# 23D_ESC_DRIVER.net
KiCad netlist of a schematic drawn in Altium Designer
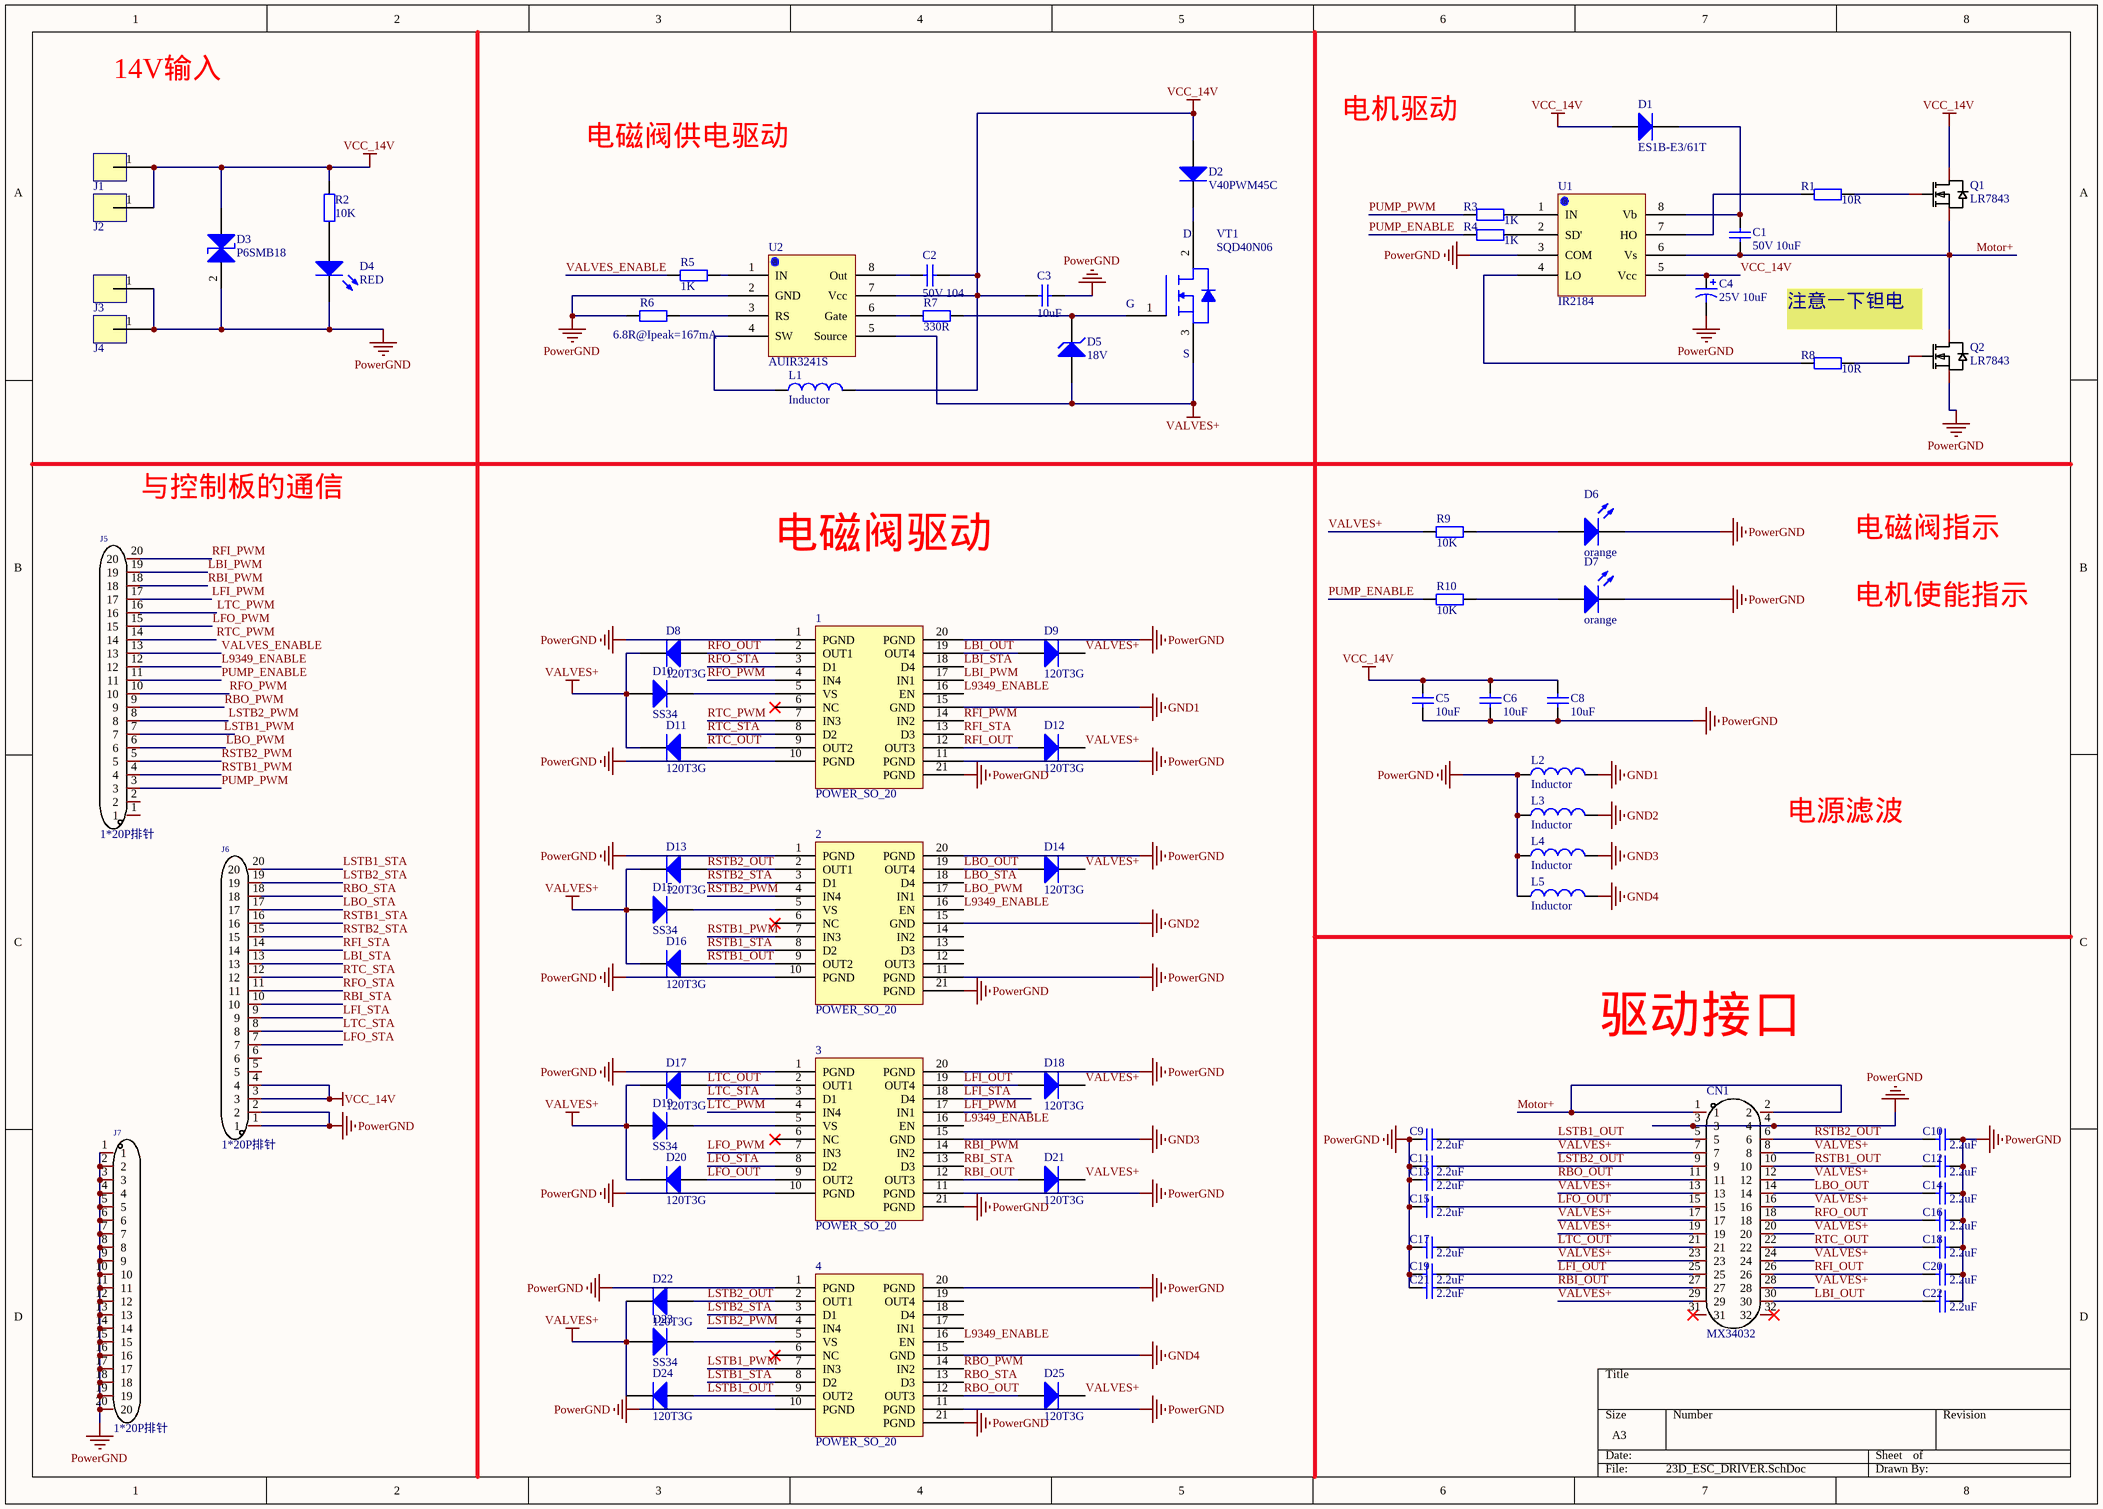
[diagram p0: 23D_ESC_DRIVER.SchDoc]

(export (version "E")
  (design (tool "Eeschema 10.0.6"))
  (components
    (comp (ref "1")
      (value "POWER_SO_20")
      (footprint "POWERSO-20_self_with3D_USEable:POWERSO-20_L15.9-W11.0-P1.27-LS14.2-BL-EP")
      (libsource (lib "PowerSO-20") (part "POWER_SO_20"))
    )
    (comp (ref "2")
      (value "POWER_SO_20")
      (footprint "POWERSO-20_self_with3D_USEable:POWERSO-20_L15.9-W11.0-P1.27-LS14.2-BL-EP")
      (libsource (lib "PowerSO-20") (part "POWER_SO_20"))
    )
    (comp (ref "3")
      (value "POWER_SO_20")
      (footprint "POWERSO-20_self_with3D_USEable:POWERSO-20_L15.9-W11.0-P1.27-LS14.2-BL-EP")
      (libsource (lib "PowerSO-20") (part "POWER_SO_20"))
    )
    (comp (ref "4")
      (value "POWER_SO_20")
      (footprint "POWERSO-20_self_with3D_USEable:POWERSO-20_L15.9-W11.0-P1.27-LS14.2-BL-EP")
      (libsource (lib "PowerSO-20") (part "POWER_SO_20"))
    )
    (comp (ref "C1")
      (value "50V 10uF")
      (footprint "C 0805")
      (description "无极性电容")
      (libsource (lib "HRT_D Schlib") (part "Cap"))
    )
    (comp (ref "C2")
      (value "50V 104")
      (footprint "C 0805")
      (description "无极性电容")
      (libsource (lib "HRT_D Schlib") (part "Cap"))
    )
    (comp (ref "C3")
      (value "10uF")
      (footprint "C 0805")
      (description "无极性电容")
      (libsource (lib "HRT_D Schlib") (part "Cap"))
    )
    (comp (ref "C4")
      (value "25V 10uF")
      (footprint "CP 3528B")
      (description "极性电容")
      (libsource (lib "ER100_ESC") (part "Cap_Pol"))
    )
    (comp (ref "C5")
      (value "10uF")
      (footprint "C 0805")
      (description "无极性电容")
      (libsource (lib "HRT_D Schlib") (part "Cap"))
    )
    (comp (ref "C6")
      (value "10uF")
      (footprint "C 0805")
      (description "无极性电容")
      (libsource (lib "HRT_D Schlib") (part "Cap"))
    )
    (comp (ref "C8")
      (value "10uF")
      (footprint "C 0805")
      (description "无极性电容")
      (libsource (lib "HRT_D Schlib") (part "Cap"))
    )
    (comp (ref "C9")
      (value "2.2uF")
      (footprint "C 0805")
      (description "无极性电容")
      (libsource (lib "HRT_D Schlib") (part "Cap"))
    )
    (comp (ref "C10")
      (value "2.2uF")
      (footprint "C 0805")
      (description "无极性电容")
      (libsource (lib "HRT_D Schlib") (part "Cap"))
    )
    (comp (ref "C11")
      (value "2.2uF")
      (footprint "C 0805")
      (description "无极性电容")
      (libsource (lib "HRT_D Schlib") (part "Cap"))
    )
    (comp (ref "C12")
      (value "2.2uF")
      (footprint "C 0805")
      (description "无极性电容")
      (libsource (lib "HRT_D Schlib") (part "Cap"))
    )
    (comp (ref "C13")
      (value "2.2uF")
      (footprint "C 0805")
      (description "无极性电容")
      (libsource (lib "HRT_D Schlib") (part "Cap"))
    )
    (comp (ref "C14")
      (value "2.2uF")
      (footprint "C 0805")
      (description "无极性电容")
      (libsource (lib "HRT_D Schlib") (part "Cap"))
    )
    (comp (ref "C15")
      (value "2.2uF")
      (footprint "C 0805")
      (description "无极性电容")
      (libsource (lib "HRT_D Schlib") (part "Cap"))
    )
    (comp (ref "C16")
      (value "2.2uF")
      (footprint "C 0805")
      (description "无极性电容")
      (libsource (lib "HRT_D Schlib") (part "Cap"))
    )
    (comp (ref "C17")
      (value "2.2uF")
      (footprint "C 0805")
      (description "无极性电容")
      (libsource (lib "HRT_D Schlib") (part "Cap"))
    )
    (comp (ref "C18")
      (value "2.2uF")
      (footprint "C 0805")
      (description "无极性电容")
      (libsource (lib "HRT_D Schlib") (part "Cap"))
    )
    (comp (ref "C19")
      (value "2.2uF")
      (footprint "C 0805")
      (description "无极性电容")
      (libsource (lib "HRT_D Schlib") (part "Cap"))
    )
    (comp (ref "C20")
      (value "2.2uF")
      (footprint "C 0805")
      (description "无极性电容")
      (libsource (lib "HRT_D Schlib") (part "Cap"))
    )
    (comp (ref "C21")
      (value "2.2uF")
      (footprint "C 0805")
      (description "无极性电容")
      (libsource (lib "HRT_D Schlib") (part "Cap"))
    )
    (comp (ref "C22")
      (value "2.2uF")
      (footprint "C 0805")
      (description "无极性电容")
      (libsource (lib "HRT_D Schlib") (part "Cap"))
    )
    (comp (ref "CN1")
      (value "MX34032NF2")
      (footprint "CONN-TH_MX34032NF2")
      (description "间距:2.2mm;插针结构:2x16P;排数:2;每排PIN数:16;行距:3mm;公母:公型插针;安装方式:弯插;")
      (fields (field (name "MANUFACTURER") "JAE(日本航空电子)") (field (name "NAME") "MX34032"))
      (libsource (lib "MX34032") (part "MX34032NF2"))
    )
    (comp (ref "D1")
      (value "ES1B-E3/61T")
      (footprint "DO-214")
      (description "二极管")
      (libsource (lib "ER100_ESC") (part "Diode"))
    )
    (comp (ref "D2")
      (value "V40PWM45C")
      (footprint "TO252_DIO")
      (description "二极管")
      (libsource (lib "ER100_ESC") (part "Diode"))
    )
    (comp (ref "D3")
      (value "P6SMB18")
      (footprint "DO-214AA")
      (description "BiDir TVS Diode")
      (libsource (lib "ER100_ESC") (part "P6SMBXX"))
    )
    (comp (ref "D4")
      (value "RED")
      (footprint "LED_0805")
      (description "发光二极管")
      (libsource (lib "ESC_control") (part "LED"))
    )
    (comp (ref "D5") (value "18V") (footprint "LL34") (libsource (lib "ER100_ESC") (part "Diode_Zener")))
    (comp (ref "D6")
      (value "orange")
      (footprint "LED_0805")
      (description "发光二极管")
      (libsource (lib "ESC_control") (part "LED"))
    )
    (comp (ref "D7")
      (value "orange")
      (footprint "LED_0805")
      (description "发光二极管")
      (libsource (lib "ESC_control") (part "LED"))
    )
    (comp (ref "D8")
      (value "120T3G")
      (footprint "DO-214")
      (description "二极管")
      (libsource (lib "ER100_ESC") (part "Diode"))
    )
    (comp (ref "D9")
      (value "120T3G")
      (footprint "DO-214")
      (description "二极管")
      (libsource (lib "ER100_ESC") (part "Diode"))
    )
    (comp (ref "D10")
      (value "SS34")
      (footprint "DO-214")
      (description "二极管")
      (libsource (lib "ESC_control") (part "Diode"))
    )
    (comp (ref "D11")
      (value "120T3G")
      (footprint "DO-214")
      (description "二极管")
      (libsource (lib "ER100_ESC") (part "Diode"))
    )
    (comp (ref "D12")
      (value "120T3G")
      (footprint "DO-214")
      (description "二极管")
      (libsource (lib "ER100_ESC") (part "Diode"))
    )
    (comp (ref "D13")
      (value "120T3G")
      (footprint "DO-214")
      (description "二极管")
      (libsource (lib "ER100_ESC") (part "Diode"))
    )
    (comp (ref "D14")
      (value "120T3G")
      (footprint "DO-214")
      (description "二极管")
      (libsource (lib "ER100_ESC") (part "Diode"))
    )
    (comp (ref "D15")
      (value "SS34")
      (footprint "DO-214")
      (description "二极管")
      (libsource (lib "ESC_control") (part "Diode"))
    )
    (comp (ref "D16")
      (value "120T3G")
      (footprint "DO-214")
      (description "二极管")
      (libsource (lib "ER100_ESC") (part "Diode"))
    )
    (comp (ref "D17")
      (value "120T3G")
      (footprint "DO-214")
      (description "二极管")
      (libsource (lib "ER100_ESC") (part "Diode"))
    )
    (comp (ref "D18")
      (value "120T3G")
      (footprint "DO-214")
      (description "二极管")
      (libsource (lib "ER100_ESC") (part "Diode"))
    )
    (comp (ref "D19")
      (value "SS34")
      (footprint "DO-214")
      (description "二极管")
      (libsource (lib "ESC_control") (part "Diode"))
    )
    (comp (ref "D20")
      (value "120T3G")
      (footprint "DO-214")
      (description "二极管")
      (libsource (lib "ER100_ESC") (part "Diode"))
    )
    (comp (ref "D21")
      (value "120T3G")
      (footprint "DO-214")
      (description "二极管")
      (libsource (lib "ER100_ESC") (part "Diode"))
    )
    (comp (ref "D22")
      (value "120T3G")
      (footprint "DO-214")
      (description "二极管")
      (libsource (lib "ER100_ESC") (part "Diode"))
    )
    (comp (ref "D23")
      (value "SS34")
      (footprint "DO-214")
      (description "二极管")
      (libsource (lib "ESC_control") (part "Diode"))
    )
    (comp (ref "D24")
      (value "120T3G")
      (footprint "DO-214")
      (description "二极管")
      (libsource (lib "ER100_ESC") (part "Diode"))
    )
    (comp (ref "D25")
      (value "120T3G")
      (footprint "DO-214")
      (description "二极管")
      (libsource (lib "ER100_ESC") (part "Diode"))
    )
    (comp (ref "J1")
      (value "SMT_Connector")
      (footprint "SMT_Connector")
      (description "表贴接线端")
      (libsource (lib "ER100_ESC") (part "SMT_Connector"))
    )
    (comp (ref "J2")
      (value "SMT_Connector")
      (footprint "SMT_Connector")
      (description "表贴接线端")
      (libsource (lib "ER100_ESC") (part "SMT_Connector"))
    )
    (comp (ref "J3")
      (value "SMT_Connector")
      (footprint "SMT_Connector")
      (description "表贴接线端")
      (libsource (lib "ER100_ESC") (part "SMT_Connector"))
    )
    (comp (ref "J4")
      (value "SMT_Connector")
      (footprint "SMT_Connector")
      (description "表贴接线端")
      (libsource (lib "ER100_ESC") (part "SMT_Connector"))
    )
    (comp (ref "J5")
      (value "2.54-1*20P直针")
      (footprint "HDR-TH_20P-P2.54-V-M-1")
      (fields (field (name "MANUFACTURER") "BOOMELE(博穆精密)") (field (name "NAME") "1*20P排针"))
      (libsource (lib "20P排针2.54mm") (part "2.54-1*20P直针"))
    )
    (comp (ref "J6")
      (value "2.54-1*20P直针")
      (footprint "HDR-TH_20P-P2.54-V-M-1")
      (fields (field (name "MANUFACTURER") "BOOMELE(博穆精密)") (field (name "NAME") "1*20P排针"))
      (libsource (lib "20P排针2.54mm") (part "2.54-1*20P直针"))
    )
    (comp (ref "J7")
      (value "2.54-1*20P直针")
      (footprint "HDR2.54-LI-20P")
      (fields (field (name "MANUFACTURER") "BOOMELE(博穆精密)") (field (name "NAME") "1*20P排针"))
      (libsource (lib "20P排针2.54mm") (part "2.54-1*20P直针"))
    )
    (comp (ref "L1")
      (value "Inductor")
      (footprint "L 0805")
      (description "电感")
      (libsource (lib "HRT_D Schlib") (part "Inductor"))
    )
    (comp (ref "L2")
      (value "Inductor")
      (footprint "L 0805")
      (description "电感")
      (libsource (lib "HRT_D Schlib") (part "Inductor"))
    )
    (comp (ref "L3")
      (value "Inductor")
      (footprint "L 0805")
      (description "电感")
      (libsource (lib "HRT_D Schlib") (part "Inductor"))
    )
    (comp (ref "L4")
      (value "Inductor")
      (footprint "L 0805")
      (description "电感")
      (libsource (lib "HRT_D Schlib") (part "Inductor"))
    )
    (comp (ref "L5")
      (value "Inductor")
      (footprint "L 0805")
      (description "电感")
      (libsource (lib "HRT_D Schlib") (part "Inductor"))
    )
    (comp (ref "Q1")
      (value "LR7843-VB")
      (footprint "TO-252-2_L6.6-W6.1-P4.58-LS9.9-BR")
      (description "类型:N沟道;漏源电压(Vdss):30V;连续漏极电流(Id):120A;导通电阻(RDS(on)@Vgs,Id):2.3mΩ@10V,120A;")
      (fields (field (name "MANUFACTURER") "VBsemi(微碧)") (field (name "NAME") "LR7843"))
      (libsource (lib "LR7843") (part "LR7843-VB"))
    )
    (comp (ref "Q2")
      (value "LR7843-VB")
      (footprint "TO-252-2_L6.6-W6.1-P4.58-LS9.9-BR")
      (description "类型:N沟道;漏源电压(Vdss):30V;连续漏极电流(Id):120A;导通电阻(RDS(on)@Vgs,Id):2.3mΩ@10V,120A;")
      (fields (field (name "MANUFACTURER") "VBsemi(微碧)") (field (name "NAME") "LR7843"))
      (libsource (lib "LR7843") (part "LR7843-VB"))
    )
    (comp (ref "R1")
      (value "10R")
      (footprint "R 0805")
      (description "电阻")
      (libsource (lib "HRT_D Schlib") (part "Resistor"))
    )
    (comp (ref "R2")
      (value "10K")
      (footprint "R 0805")
      (description "电阻")
      (libsource (lib "") (part "Resistor_1"))
    )
    (comp (ref "R3")
      (value "1K")
      (footprint "R 0805")
      (description "电阻")
      (libsource (lib "HRT_D Schlib") (part "Resistor"))
    )
    (comp (ref "R4")
      (value "1K")
      (footprint "R 0805")
      (description "电阻")
      (libsource (lib "HRT_D Schlib") (part "Resistor"))
    )
    (comp (ref "R5")
      (value "1K")
      (footprint "R 0805")
      (description "电阻")
      (libsource (lib "HRT_D Schlib") (part "Resistor"))
    )
    (comp (ref "R6")
      (value "6.8R@Ipeak=167mA")
      (footprint "R 0805")
      (description "电阻")
      (libsource (lib "HRT_D Schlib") (part "Resistor"))
    )
    (comp (ref "R7")
      (value "330R")
      (footprint "R 0805")
      (description "电阻")
      (libsource (lib "HRT_D Schlib") (part "Resistor"))
    )
    (comp (ref "R8")
      (value "10R")
      (footprint "R 0805")
      (description "电阻")
      (libsource (lib "HRT_D Schlib") (part "Resistor"))
    )
    (comp (ref "R9")
      (value "10K")
      (footprint "R 0805")
      (description "电阻")
      (libsource (lib "HRT_D Schlib") (part "Resistor"))
    )
    (comp (ref "R10")
      (value "10K")
      (footprint "R 0805")
      (description "电阻")
      (libsource (lib "HRT_D Schlib") (part "Resistor"))
    )
    (comp (ref "U1")
      (value "IR2184")
      (footprint "SOP8")
      (description "Half-Bridge Gate Driver")
      (libsource (lib "ER100_ESC") (part "IR2184"))
    )
    (comp (ref "U2")
      (value "AUIR3241S")
      (footprint "SOP8")
      (description "B2B MOSFET Driver")
      (libsource (lib "ER100_ESC") (part "AUIR3241S"))
    )
    (comp (ref "VT1")
      (value "SQD40N06")
      (footprint "TO252")
      (libsource (lib "ER100_ESC") (part "PowerMos_N"))
    )
  )
  (nets
    (net (code "1") (name "/L9349_ENABLE") (class "Default")
      (node (ref "1") (pin "16") (pinfunction "EN_16") (pintype "passive"))
      (node (ref "2") (pin "16") (pinfunction "EN_16") (pintype "passive"))
      (node (ref "3") (pin "16") (pinfunction "EN_16") (pintype "passive"))
      (node (ref "4") (pin "16") (pinfunction "EN_16") (pintype "passive"))
      (node (ref "J5") (pin "12") (pinfunction "12_12") (pintype "passive"))
    )
    (net (code "2") (name "/LBI_OUT") (class "Default")
      (node (ref "1") (pin "19") (pinfunction "OUT4_19") (pintype "passive"))
      (node (ref "C22") (pin "1") (pinfunction "1_1") (pintype "passive"))
      (node (ref "CN1") (pin "30") (pinfunction "30_30") (pintype "passive"))
      (node (ref "D9") (pin "1") (pinfunction "A_1") (pintype "passive"))
    )
    (net (code "3") (name "/LBI_PWM") (class "Default")
      (node (ref "1") (pin "17") (pinfunction "IN1_17") (pintype "passive"))
      (node (ref "J5") (pin "19") (pinfunction "19_19") (pintype "passive"))
    )
    (net (code "4") (name "/LBI_STA") (class "Default")
      (node (ref "1") (pin "18") (pinfunction "D4_18") (pintype "passive"))
      (node (ref "J6") (pin "13") (pinfunction "13_13") (pintype "passive"))
    )
    (net (code "5") (name "/LBO_OUT") (class "Default")
      (node (ref "2") (pin "19") (pinfunction "OUT4_19") (pintype "passive"))
      (node (ref "C14") (pin "1") (pinfunction "1_1") (pintype "passive"))
      (node (ref "CN1") (pin "14") (pinfunction "14_14") (pintype "passive"))
      (node (ref "D14") (pin "1") (pinfunction "A_1") (pintype "passive"))
    )
    (net (code "6") (name "/LBO_PWM") (class "Default")
      (node (ref "2") (pin "17") (pinfunction "IN1_17") (pintype "passive"))
      (node (ref "J5") (pin "6") (pinfunction "6_6") (pintype "passive"))
    )
    (net (code "7") (name "/LBO_STA") (class "Default")
      (node (ref "2") (pin "18") (pinfunction "D4_18") (pintype "passive"))
      (node (ref "J6") (pin "17") (pinfunction "17_17") (pintype "passive"))
    )
    (net (code "8") (name "/LFI_OUT") (class "Default")
      (node (ref "3") (pin "19") (pinfunction "OUT4_19") (pintype "passive"))
      (node (ref "C19") (pin "2") (pinfunction "2_2") (pintype "passive"))
      (node (ref "CN1") (pin "25") (pinfunction "25_25") (pintype "passive"))
      (node (ref "D18") (pin "1") (pinfunction "A_1") (pintype "passive"))
    )
    (net (code "9") (name "/LFI_PWM") (class "Default")
      (node (ref "3") (pin "17") (pinfunction "IN1_17") (pintype "passive"))
      (node (ref "J5") (pin "17") (pinfunction "17_17") (pintype "passive"))
    )
    (net (code "10") (name "/LFI_STA") (class "Default")
      (node (ref "3") (pin "18") (pinfunction "D4_18") (pintype "passive"))
      (node (ref "J6") (pin "9") (pinfunction "9_9") (pintype "passive"))
    )
    (net (code "11") (name "/LFO_OUT") (class "Default")
      (node (ref "3") (pin "9") (pinfunction "OUT2_9") (pintype "passive"))
      (node (ref "C15") (pin "2") (pinfunction "2_2") (pintype "passive"))
      (node (ref "CN1") (pin "15") (pinfunction "15_15") (pintype "passive"))
      (node (ref "D20") (pin "1") (pinfunction "A_1") (pintype "passive"))
    )
    (net (code "12") (name "/LFO_PWM") (class "Default")
      (node (ref "3") (pin "7") (pinfunction "IN3_7") (pintype "passive"))
      (node (ref "J5") (pin "15") (pinfunction "15_15") (pintype "passive"))
    )
    (net (code "13") (name "/LFO_STA") (class "Default")
      (node (ref "3") (pin "8") (pinfunction "D2_8") (pintype "passive"))
      (node (ref "J6") (pin "7") (pinfunction "7_7") (pintype "passive"))
    )
    (net (code "14") (name "/LSTB1_OUT") (class "Default")
      (node (ref "4") (pin "9") (pinfunction "OUT2_9") (pintype "passive"))
      (node (ref "C9") (pin "2") (pinfunction "2_2") (pintype "passive"))
      (node (ref "CN1") (pin "5") (pinfunction "5_5") (pintype "passive"))
      (node (ref "D24") (pin "1") (pinfunction "A_1") (pintype "passive"))
    )
    (net (code "15") (name "/LSTB1_PWM") (class "Default")
      (node (ref "4") (pin "7") (pinfunction "IN3_7") (pintype "passive"))
      (node (ref "J5") (pin "7") (pinfunction "7_7") (pintype "passive"))
    )
    (net (code "16") (name "/LSTB1_STA") (class "Default")
      (node (ref "4") (pin "8") (pinfunction "D2_8") (pintype "passive"))
      (node (ref "J6") (pin "20") (pinfunction "20_20") (pintype "passive"))
    )
    (net (code "17") (name "/LSTB2_OUT") (class "Default")
      (node (ref "4") (pin "2") (pinfunction "OUT1_2") (pintype "passive"))
      (node (ref "C11") (pin "2") (pinfunction "2_2") (pintype "passive"))
      (node (ref "CN1") (pin "9") (pinfunction "9_9") (pintype "passive"))
      (node (ref "D22") (pin "1") (pinfunction "A_1") (pintype "passive"))
    )
    (net (code "18") (name "/LSTB2_PWM") (class "Default")
      (node (ref "4") (pin "4") (pinfunction "IN4_4") (pintype "passive"))
      (node (ref "J5") (pin "8") (pinfunction "8_8") (pintype "passive"))
    )
    (net (code "19") (name "/LSTB2_STA") (class "Default")
      (node (ref "4") (pin "3") (pinfunction "D1_3") (pintype "passive"))
      (node (ref "J6") (pin "19") (pinfunction "19_19") (pintype "passive"))
    )
    (net (code "20") (name "/LTC_OUT") (class "Default")
      (node (ref "3") (pin "2") (pinfunction "OUT1_2") (pintype "passive"))
      (node (ref "C17") (pin "2") (pinfunction "2_2") (pintype "passive"))
      (node (ref "CN1") (pin "21") (pinfunction "21_21") (pintype "passive"))
      (node (ref "D17") (pin "1") (pinfunction "A_1") (pintype "passive"))
    )
    (net (code "21") (name "/LTC_PWM") (class "Default")
      (node (ref "3") (pin "4") (pinfunction "IN4_4") (pintype "passive"))
      (node (ref "J5") (pin "16") (pinfunction "16_16") (pintype "passive"))
    )
    (net (code "22") (name "/LTC_STA") (class "Default")
      (node (ref "3") (pin "3") (pinfunction "D1_3") (pintype "passive"))
      (node (ref "J6") (pin "8") (pinfunction "8_8") (pintype "passive"))
    )
    (net (code "23") (name "/Motor+") (class "Default")
      (node (ref "C1") (pin "1") (pinfunction "1_1") (pintype "passive"))
      (node (ref "CN1") (pin "1") (pinfunction "1_1") (pintype "passive"))
      (node (ref "CN1") (pin "2") (pinfunction "2_2") (pintype "passive"))
      (node (ref "Q1") (pin "3") (pinfunction "S_3") (pintype "passive"))
      (node (ref "Q2") (pin "2") (pinfunction "D_2") (pintype "passive"))
      (node (ref "U1") (pin "6") (pinfunction "Vs_6") (pintype "passive"))
    )
    (net (code "24") (name "/PUMP_ENABLE") (class "Default")
      (node (ref "J5") (pin "11") (pinfunction "11_11") (pintype "passive"))
      (node (ref "R10") (pin "1") (pinfunction "1_1") (pintype "passive"))
      (node (ref "R4") (pin "1") (pinfunction "1_1") (pintype "passive"))
    )
    (net (code "25") (name "/PUMP_PWM") (class "Default")
      (node (ref "J5") (pin "3") (pinfunction "3_3") (pintype "passive"))
      (node (ref "R3") (pin "1") (pinfunction "1_1") (pintype "passive"))
    )
    (net (code "26") (name "/RBI_OUT") (class "Default")
      (node (ref "3") (pin "12") (pinfunction "OUT3_12") (pintype "passive"))
      (node (ref "C21") (pin "2") (pinfunction "2_2") (pintype "passive"))
      (node (ref "CN1") (pin "27") (pinfunction "27_27") (pintype "passive"))
      (node (ref "D21") (pin "1") (pinfunction "A_1") (pintype "passive"))
    )
    (net (code "27") (name "/RBI_PWM") (class "Default")
      (node (ref "3") (pin "14") (pinfunction "IN2_14") (pintype "passive"))
      (node (ref "J5") (pin "18") (pinfunction "18_18") (pintype "passive"))
    )
    (net (code "28") (name "/RBI_STA") (class "Default")
      (node (ref "3") (pin "13") (pinfunction "D3_13") (pintype "passive"))
      (node (ref "J6") (pin "10") (pinfunction "10_10") (pintype "passive"))
    )
    (net (code "29") (name "/RBO_OUT") (class "Default")
      (node (ref "4") (pin "12") (pinfunction "OUT3_12") (pintype "passive"))
      (node (ref "C13") (pin "2") (pinfunction "2_2") (pintype "passive"))
      (node (ref "CN1") (pin "11") (pinfunction "11_11") (pintype "passive"))
      (node (ref "D25") (pin "1") (pinfunction "A_1") (pintype "passive"))
    )
    (net (code "30") (name "/RBO_PWM") (class "Default")
      (node (ref "4") (pin "14") (pinfunction "IN2_14") (pintype "passive"))
      (node (ref "J5") (pin "9") (pinfunction "9_9") (pintype "passive"))
    )
    (net (code "31") (name "/RBO_STA") (class "Default")
      (node (ref "4") (pin "13") (pinfunction "D3_13") (pintype "passive"))
      (node (ref "J6") (pin "18") (pinfunction "18_18") (pintype "passive"))
    )
    (net (code "32") (name "/RFI_OUT") (class "Default")
      (node (ref "1") (pin "12") (pinfunction "OUT3_12") (pintype "passive"))
      (node (ref "C20") (pin "1") (pinfunction "1_1") (pintype "passive"))
      (node (ref "CN1") (pin "26") (pinfunction "26_26") (pintype "passive"))
      (node (ref "D12") (pin "1") (pinfunction "A_1") (pintype "passive"))
    )
    (net (code "33") (name "/RFI_PWM") (class "Default")
      (node (ref "1") (pin "14") (pinfunction "IN2_14") (pintype "passive"))
      (node (ref "J5") (pin "20") (pinfunction "20_20") (pintype "passive"))
    )
    (net (code "34") (name "/RFI_STA") (class "Default")
      (node (ref "1") (pin "13") (pinfunction "D3_13") (pintype "passive"))
      (node (ref "J6") (pin "14") (pinfunction "14_14") (pintype "passive"))
    )
    (net (code "35") (name "/RFO_OUT") (class "Default")
      (node (ref "1") (pin "2") (pinfunction "OUT1_2") (pintype "passive"))
      (node (ref "C16") (pin "1") (pinfunction "1_1") (pintype "passive"))
      (node (ref "CN1") (pin "18") (pinfunction "18_18") (pintype "passive"))
      (node (ref "D8") (pin "1") (pinfunction "A_1") (pintype "passive"))
    )
    (net (code "36") (name "/RFO_PWM") (class "Default")
      (node (ref "1") (pin "4") (pinfunction "IN4_4") (pintype "passive"))
      (node (ref "J5") (pin "10") (pinfunction "10_10") (pintype "passive"))
    )
    (net (code "37") (name "/RFO_STA") (class "Default")
      (node (ref "1") (pin "3") (pinfunction "D1_3") (pintype "passive"))
      (node (ref "J6") (pin "11") (pinfunction "11_11") (pintype "passive"))
    )
    (net (code "38") (name "/RSTB1_OUT") (class "Default")
      (node (ref "2") (pin "9") (pinfunction "OUT2_9") (pintype "passive"))
      (node (ref "C12") (pin "1") (pinfunction "1_1") (pintype "passive"))
      (node (ref "CN1") (pin "10") (pinfunction "10_10") (pintype "passive"))
      (node (ref "D16") (pin "1") (pinfunction "A_1") (pintype "passive"))
    )
    (net (code "39") (name "/RSTB1_PWM") (class "Default")
      (node (ref "2") (pin "7") (pinfunction "IN3_7") (pintype "passive"))
      (node (ref "J5") (pin "4") (pinfunction "4_4") (pintype "passive"))
    )
    (net (code "40") (name "/RSTB1_STA") (class "Default")
      (node (ref "2") (pin "8") (pinfunction "D2_8") (pintype "passive"))
      (node (ref "J6") (pin "16") (pinfunction "16_16") (pintype "passive"))
    )
    (net (code "41") (name "/RSTB2_OUT") (class "Default")
      (node (ref "2") (pin "2") (pinfunction "OUT1_2") (pintype "passive"))
      (node (ref "C10") (pin "1") (pinfunction "1_1") (pintype "passive"))
      (node (ref "CN1") (pin "6") (pinfunction "6_6") (pintype "passive"))
      (node (ref "D13") (pin "1") (pinfunction "A_1") (pintype "passive"))
    )
    (net (code "42") (name "/RSTB2_PWM") (class "Default")
      (node (ref "2") (pin "4") (pinfunction "IN4_4") (pintype "passive"))
      (node (ref "J5") (pin "5") (pinfunction "5_5") (pintype "passive"))
    )
    (net (code "43") (name "/RSTB2_STA") (class "Default")
      (node (ref "2") (pin "3") (pinfunction "D1_3") (pintype "passive"))
      (node (ref "J6") (pin "15") (pinfunction "15_15") (pintype "passive"))
    )
    (net (code "44") (name "/RTC_OUT") (class "Default")
      (node (ref "1") (pin "9") (pinfunction "OUT2_9") (pintype "passive"))
      (node (ref "C18") (pin "1") (pinfunction "1_1") (pintype "passive"))
      (node (ref "CN1") (pin "22") (pinfunction "22_22") (pintype "passive"))
      (node (ref "D11") (pin "1") (pinfunction "A_1") (pintype "passive"))
    )
    (net (code "45") (name "/RTC_PWM") (class "Default")
      (node (ref "1") (pin "7") (pinfunction "IN3_7") (pintype "passive"))
      (node (ref "J5") (pin "14") (pinfunction "14_14") (pintype "passive"))
    )
    (net (code "46") (name "/RTC_STA") (class "Default")
      (node (ref "1") (pin "8") (pinfunction "D2_8") (pintype "passive"))
      (node (ref "J6") (pin "12") (pinfunction "12_12") (pintype "passive"))
    )
    (net (code "47") (name "/VALVES_ENABLE") (class "Default")
      (node (ref "J5") (pin "13") (pinfunction "13_13") (pintype "passive"))
      (node (ref "R5") (pin "1") (pinfunction "1_1") (pintype "passive"))
    )
    (net (code "48") (name "GND1") (class "Default")
      (node (ref "1") (pin "15") (pinfunction "GND_15") (pintype "passive"))
      (node (ref "L2") (pin "2") (pinfunction "2_2") (pintype "passive"))
    )
    (net (code "49") (name "GND2") (class "Default")
      (node (ref "2") (pin "15") (pinfunction "GND_15") (pintype "passive"))
      (node (ref "L3") (pin "2") (pinfunction "2_2") (pintype "passive"))
    )
    (net (code "50") (name "GND3") (class "Default")
      (node (ref "3") (pin "15") (pinfunction "GND_15") (pintype "passive"))
      (node (ref "L4") (pin "2") (pinfunction "2_2") (pintype "passive"))
    )
    (net (code "51") (name "GND4") (class "Default")
      (node (ref "4") (pin "15") (pinfunction "GND_15") (pintype "passive"))
      (node (ref "L5") (pin "2") (pinfunction "2_2") (pintype "passive"))
    )
    (net (code "52") (name "Net-(1-VS)") (class "Default")
      (node (ref "1") (pin "5") (pinfunction "VS_5") (pintype "passive"))
      (node (ref "D10") (pin "2") (pinfunction "K_2") (pintype "passive"))
    )
    (net (code "53") (name "Net-(2-VS)") (class "Default")
      (node (ref "2") (pin "5") (pinfunction "VS_5") (pintype "passive"))
      (node (ref "D15") (pin "2") (pinfunction "K_2") (pintype "passive"))
    )
    (net (code "54") (name "Net-(3-VS)") (class "Default")
      (node (ref "3") (pin "5") (pinfunction "VS_5") (pintype "passive"))
      (node (ref "D19") (pin "2") (pinfunction "K_2") (pintype "passive"))
    )
    (net (code "55") (name "Net-(4-VS)") (class "Default")
      (node (ref "4") (pin "5") (pinfunction "VS_5") (pintype "passive"))
      (node (ref "D23") (pin "2") (pinfunction "K_2") (pintype "passive"))
    )
    (net (code "56") (name "Net-(D1-K)") (class "Default")
      (node (ref "C1") (pin "2") (pinfunction "2_2") (pintype "passive"))
      (node (ref "D1") (pin "2") (pinfunction "K_2") (pintype "passive"))
      (node (ref "U1") (pin "8") (pinfunction "Vb_8") (pintype "passive"))
    )
    (net (code "57") (name "Net-(D2-K)") (class "Default")
      (node (ref "D2") (pin "2") (pinfunction "K_2") (pintype "passive"))
      (node (ref "VT1") (pin "2") (pinfunction "2_2") (pintype "passive"))
    )
    (net (code "58") (name "Net-(D4-A)") (class "Default")
      (node (ref "D4") (pin "1") (pinfunction "A_1") (pintype "passive"))
      (node (ref "R2") (pin "1") (pinfunction "1_1") (pintype "passive"))
    )
    (net (code "59") (name "Net-(D5-K)") (class "Default")
      (node (ref "D5") (pin "2") (pinfunction "K_2") (pintype "passive"))
      (node (ref "R7") (pin "2") (pinfunction "2_2") (pintype "passive"))
      (node (ref "VT1") (pin "1") (pinfunction "G_1") (pintype "passive"))
    )
    (net (code "60") (name "Net-(D6-A)") (class "Default")
      (node (ref "D6") (pin "1") (pinfunction "A_1") (pintype "passive"))
      (node (ref "R9") (pin "2") (pinfunction "2_2") (pintype "passive"))
    )
    (net (code "61") (name "Net-(D7-A)") (class "Default")
      (node (ref "D7") (pin "1") (pinfunction "A_1") (pintype "passive"))
      (node (ref "R10") (pin "2") (pinfunction "2_2") (pintype "passive"))
    )
    (net (code "62") (name "Net-(Q1-G)") (class "Default")
      (node (ref "Q1") (pin "1") (pinfunction "G_1") (pintype "passive"))
      (node (ref "R1") (pin "2") (pinfunction "2_2") (pintype "passive"))
    )
    (net (code "63") (name "Net-(Q2-G)") (class "Default")
      (node (ref "Q2") (pin "1") (pinfunction "G_1") (pintype "passive"))
      (node (ref "R8") (pin "2") (pinfunction "2_2") (pintype "passive"))
    )
    (net (code "64") (name "Net-(U1-HO)") (class "Default")
      (node (ref "R1") (pin "1") (pinfunction "1_1") (pintype "passive"))
      (node (ref "U1") (pin "7") (pinfunction "HO_7") (pintype "passive"))
    )
    (net (code "65") (name "Net-(U1-IN)") (class "Default")
      (node (ref "R3") (pin "2") (pinfunction "2_2") (pintype "passive"))
      (node (ref "U1") (pin "1") (pinfunction "IN_1") (pintype "passive"))
    )
    (net (code "66") (name "Net-(U1-LO)") (class "Default")
      (node (ref "R8") (pin "1") (pinfunction "1_1") (pintype "passive"))
      (node (ref "U1") (pin "4") (pinfunction "LO_4") (pintype "passive"))
    )
    (net (code "67") (name "Net-(U1-SD')") (class "Default")
      (node (ref "R4") (pin "2") (pinfunction "2_2") (pintype "passive"))
      (node (ref "U1") (pin "2") (pinfunction "SD'_2") (pintype "passive"))
    )
    (net (code "68") (name "Net-(U2-Gate)") (class "Default")
      (node (ref "R7") (pin "1") (pinfunction "1_1") (pintype "passive"))
      (node (ref "U2") (pin "6") (pinfunction "Gate_6") (pintype "passive"))
    )
    (net (code "69") (name "Net-(U2-IN)") (class "Default")
      (node (ref "R5") (pin "2") (pinfunction "2_2") (pintype "passive"))
      (node (ref "U2") (pin "1") (pinfunction "IN_1") (pintype "passive"))
    )
    (net (code "70") (name "Net-(U2-Out)") (class "Default")
      (node (ref "C2") (pin "1") (pinfunction "1_1") (pintype "passive"))
      (node (ref "U2") (pin "8") (pinfunction "Out_8") (pintype "passive"))
    )
    (net (code "71") (name "Net-(U2-RS)") (class "Default")
      (node (ref "R6") (pin "2") (pinfunction "2_2") (pintype "passive"))
      (node (ref "U2") (pin "3") (pinfunction "RS_3") (pintype "passive"))
    )
    (net (code "72") (name "Net-(U2-SW)") (class "Default")
      (node (ref "L1") (pin "1") (pinfunction "1_1") (pintype "passive"))
      (node (ref "U2") (pin "4") (pinfunction "SW_4") (pintype "passive"))
    )
    (net (code "73") (name "PowerGND") (class "Default")
      (node (ref "1") (pin "1") (pinfunction "PGND_1") (pintype "passive"))
      (node (ref "1") (pin "10") (pinfunction "PGND_10") (pintype "passive"))
      (node (ref "1") (pin "11") (pinfunction "PGND_11") (pintype "passive"))
      (node (ref "1") (pin "20") (pinfunction "PGND_20") (pintype "passive"))
      (node (ref "1") (pin "21") (pinfunction "PGND_21") (pintype "passive"))
      (node (ref "2") (pin "1") (pinfunction "PGND_1") (pintype "passive"))
      (node (ref "2") (pin "10") (pinfunction "PGND_10") (pintype "passive"))
      (node (ref "2") (pin "11") (pinfunction "PGND_11") (pintype "passive"))
      (node (ref "2") (pin "20") (pinfunction "PGND_20") (pintype "passive"))
      (node (ref "2") (pin "21") (pinfunction "PGND_21") (pintype "passive"))
      (node (ref "3") (pin "1") (pinfunction "PGND_1") (pintype "passive"))
      (node (ref "3") (pin "10") (pinfunction "PGND_10") (pintype "passive"))
      (node (ref "3") (pin "11") (pinfunction "PGND_11") (pintype "passive"))
      (node (ref "3") (pin "20") (pinfunction "PGND_20") (pintype "passive"))
      (node (ref "3") (pin "21") (pinfunction "PGND_21") (pintype "passive"))
      (node (ref "4") (pin "1") (pinfunction "PGND_1") (pintype "passive"))
      (node (ref "4") (pin "10") (pinfunction "PGND_10") (pintype "passive"))
      (node (ref "4") (pin "11") (pinfunction "PGND_11") (pintype "passive"))
      (node (ref "4") (pin "20") (pinfunction "PGND_20") (pintype "passive"))
      (node (ref "4") (pin "21") (pinfunction "PGND_21") (pintype "passive"))
      (node (ref "C10") (pin "2") (pinfunction "2_2") (pintype "passive"))
      (node (ref "C11") (pin "1") (pinfunction "1_1") (pintype "passive"))
      (node (ref "C12") (pin "2") (pinfunction "2_2") (pintype "passive"))
      (node (ref "C13") (pin "1") (pinfunction "1_1") (pintype "passive"))
      (node (ref "C14") (pin "2") (pinfunction "2_2") (pintype "passive"))
      (node (ref "C15") (pin "1") (pinfunction "1_1") (pintype "passive"))
      (node (ref "C16") (pin "2") (pinfunction "2_2") (pintype "passive"))
      (node (ref "C17") (pin "1") (pinfunction "1_1") (pintype "passive"))
      (node (ref "C18") (pin "2") (pinfunction "2_2") (pintype "passive"))
      (node (ref "C19") (pin "1") (pinfunction "1_1") (pintype "passive"))
      (node (ref "C20") (pin "2") (pinfunction "2_2") (pintype "passive"))
      (node (ref "C21") (pin "1") (pinfunction "1_1") (pintype "passive"))
      (node (ref "C22") (pin "2") (pinfunction "2_2") (pintype "passive"))
      (node (ref "C3") (pin "2") (pinfunction "2_2") (pintype "passive"))
      (node (ref "C4") (pin "2") (pinfunction "2_2") (pintype "passive"))
      (node (ref "C5") (pin "1") (pinfunction "1_1") (pintype "passive"))
      (node (ref "C6") (pin "1") (pinfunction "1_1") (pintype "passive"))
      (node (ref "C8") (pin "1") (pinfunction "1_1") (pintype "passive"))
      (node (ref "C9") (pin "1") (pinfunction "1_1") (pintype "passive"))
      (node (ref "CN1") (pin "3") (pinfunction "3_3") (pintype "passive"))
      (node (ref "CN1") (pin "4") (pinfunction "4_4") (pintype "passive"))
      (node (ref "D3") (pin "2") (pinfunction "K_2") (pintype "passive"))
      (node (ref "D4") (pin "2") (pinfunction "K_2") (pintype "passive"))
      (node (ref "D6") (pin "2") (pinfunction "K_2") (pintype "passive"))
      (node (ref "D7") (pin "2") (pinfunction "K_2") (pintype "passive"))
      (node (ref "J3") (pin "1") (pinfunction "1_1") (pintype "passive"))
      (node (ref "J4") (pin "1") (pinfunction "1_1") (pintype "passive"))
      (node (ref "J6") (pin "1") (pinfunction "1_1") (pintype "passive"))
      (node (ref "J6") (pin "2") (pinfunction "2_2") (pintype "passive"))
      (node (ref "J7") (pin "1") (pinfunction "1_1") (pintype "passive"))
      (node (ref "J7") (pin "10") (pinfunction "10_10") (pintype "passive"))
      (node (ref "J7") (pin "11") (pinfunction "11_11") (pintype "passive"))
      (node (ref "J7") (pin "12") (pinfunction "12_12") (pintype "passive"))
      (node (ref "J7") (pin "13") (pinfunction "13_13") (pintype "passive"))
      (node (ref "J7") (pin "14") (pinfunction "14_14") (pintype "passive"))
      (node (ref "J7") (pin "15") (pinfunction "15_15") (pintype "passive"))
      (node (ref "J7") (pin "16") (pinfunction "16_16") (pintype "passive"))
      (node (ref "J7") (pin "17") (pinfunction "17_17") (pintype "passive"))
      (node (ref "J7") (pin "18") (pinfunction "18_18") (pintype "passive"))
      (node (ref "J7") (pin "19") (pinfunction "19_19") (pintype "passive"))
      (node (ref "J7") (pin "2") (pinfunction "2_2") (pintype "passive"))
      (node (ref "J7") (pin "20") (pinfunction "20_20") (pintype "passive"))
      (node (ref "J7") (pin "3") (pinfunction "3_3") (pintype "passive"))
      (node (ref "J7") (pin "4") (pinfunction "4_4") (pintype "passive"))
      (node (ref "J7") (pin "5") (pinfunction "5_5") (pintype "passive"))
      (node (ref "J7") (pin "6") (pinfunction "6_6") (pintype "passive"))
      (node (ref "J7") (pin "7") (pinfunction "7_7") (pintype "passive"))
      (node (ref "J7") (pin "8") (pinfunction "8_8") (pintype "passive"))
      (node (ref "J7") (pin "9") (pinfunction "9_9") (pintype "passive"))
      (node (ref "L2") (pin "1") (pinfunction "1_1") (pintype "passive"))
      (node (ref "L3") (pin "1") (pinfunction "1_1") (pintype "passive"))
      (node (ref "L4") (pin "1") (pinfunction "1_1") (pintype "passive"))
      (node (ref "L5") (pin "1") (pinfunction "1_1") (pintype "passive"))
      (node (ref "Q2") (pin "3") (pinfunction "S_3") (pintype "passive"))
      (node (ref "R6") (pin "1") (pinfunction "1_1") (pintype "passive"))
      (node (ref "U1") (pin "3") (pinfunction "COM_3") (pintype "passive"))
      (node (ref "U2") (pin "2") (pinfunction "GND_2") (pintype "passive"))
    )
    (net (code "74") (name "VALVES+") (class "Default")
      (node (ref "CN1") (pin "12") (pinfunction "12_12") (pintype "passive"))
      (node (ref "CN1") (pin "13") (pinfunction "13_13") (pintype "passive"))
      (node (ref "CN1") (pin "16") (pinfunction "16_16") (pintype "passive"))
      (node (ref "CN1") (pin "17") (pinfunction "17_17") (pintype "passive"))
      (node (ref "CN1") (pin "19") (pinfunction "19_19") (pintype "passive"))
      (node (ref "CN1") (pin "20") (pinfunction "20_20") (pintype "passive"))
      (node (ref "CN1") (pin "23") (pinfunction "23_23") (pintype "passive"))
      (node (ref "CN1") (pin "24") (pinfunction "24_24") (pintype "passive"))
      (node (ref "CN1") (pin "28") (pinfunction "28_28") (pintype "passive"))
      (node (ref "CN1") (pin "29") (pinfunction "29_29") (pintype "passive"))
      (node (ref "CN1") (pin "7") (pinfunction "7_7") (pintype "passive"))
      (node (ref "CN1") (pin "8") (pinfunction "8_8") (pintype "passive"))
      (node (ref "D10") (pin "1") (pinfunction "A_1") (pintype "passive"))
      (node (ref "D11") (pin "2") (pinfunction "K_2") (pintype "passive"))
      (node (ref "D12") (pin "2") (pinfunction "K_2") (pintype "passive"))
      (node (ref "D13") (pin "2") (pinfunction "K_2") (pintype "passive"))
      (node (ref "D14") (pin "2") (pinfunction "K_2") (pintype "passive"))
      (node (ref "D15") (pin "1") (pinfunction "A_1") (pintype "passive"))
      (node (ref "D16") (pin "2") (pinfunction "K_2") (pintype "passive"))
      (node (ref "D17") (pin "2") (pinfunction "K_2") (pintype "passive"))
      (node (ref "D18") (pin "2") (pinfunction "K_2") (pintype "passive"))
      (node (ref "D19") (pin "1") (pinfunction "A_1") (pintype "passive"))
      (node (ref "D20") (pin "2") (pinfunction "K_2") (pintype "passive"))
      (node (ref "D21") (pin "2") (pinfunction "K_2") (pintype "passive"))
      (node (ref "D22") (pin "2") (pinfunction "K_2") (pintype "passive"))
      (node (ref "D23") (pin "1") (pinfunction "A_1") (pintype "passive"))
      (node (ref "D24") (pin "2") (pinfunction "K_2") (pintype "passive"))
      (node (ref "D25") (pin "2") (pinfunction "K_2") (pintype "passive"))
      (node (ref "D5") (pin "1") (pinfunction "A_1") (pintype "passive"))
      (node (ref "D8") (pin "2") (pinfunction "K_2") (pintype "passive"))
      (node (ref "D9") (pin "2") (pinfunction "K_2") (pintype "passive"))
      (node (ref "R9") (pin "1") (pinfunction "1_1") (pintype "passive"))
      (node (ref "U2") (pin "5") (pinfunction "Source_5") (pintype "passive"))
      (node (ref "VT1") (pin "3") (pinfunction "3_3") (pintype "passive"))
    )
    (net (code "75") (name "VCC_14V") (class "Default")
      (node (ref "C2") (pin "2") (pinfunction "2_2") (pintype "passive"))
      (node (ref "C3") (pin "1") (pinfunction "1_1") (pintype "passive"))
      (node (ref "C4") (pin "1") (pinfunction "1_1") (pintype "passive"))
      (node (ref "C5") (pin "2") (pinfunction "2_2") (pintype "passive"))
      (node (ref "C6") (pin "2") (pinfunction "2_2") (pintype "passive"))
      (node (ref "C8") (pin "2") (pinfunction "2_2") (pintype "passive"))
      (node (ref "D1") (pin "1") (pinfunction "A_1") (pintype "passive"))
      (node (ref "D2") (pin "1") (pinfunction "A_1") (pintype "passive"))
      (node (ref "D3") (pin "1") (pinfunction "A_1") (pintype "passive"))
      (node (ref "J1") (pin "1") (pinfunction "1_1") (pintype "passive"))
      (node (ref "J2") (pin "1") (pinfunction "1_1") (pintype "passive"))
      (node (ref "J6") (pin "3") (pinfunction "3_3") (pintype "passive"))
      (node (ref "J6") (pin "4") (pinfunction "4_4") (pintype "passive"))
      (node (ref "L1") (pin "2") (pinfunction "2_2") (pintype "passive"))
      (node (ref "Q1") (pin "2") (pinfunction "D_2") (pintype "passive"))
      (node (ref "R2") (pin "2") (pinfunction "2_2") (pintype "passive"))
      (node (ref "U1") (pin "5") (pinfunction "Vcc_5") (pintype "passive"))
      (node (ref "U2") (pin "7") (pinfunction "Vcc_7") (pintype "passive"))
    )
    (net (code "76") (name "unconnected-(1-NC-Pad6)") (class "Default")
      (node (ref "1") (pin "6") (pinfunction "NC_6") (pintype "passive+no_connect"))
    )
    (net (code "77") (name "unconnected-(2-D3-Pad13)") (class "Default")
      (node (ref "2") (pin "13") (pinfunction "D3_13") (pintype "passive"))
    )
    (net (code "78") (name "unconnected-(2-IN2-Pad14)") (class "Default")
      (node (ref "2") (pin "14") (pinfunction "IN2_14") (pintype "passive"))
    )
    (net (code "79") (name "unconnected-(2-NC-Pad6)") (class "Default")
      (node (ref "2") (pin "6") (pinfunction "NC_6") (pintype "passive+no_connect"))
    )
    (net (code "80") (name "unconnected-(2-OUT3-Pad12)") (class "Default")
      (node (ref "2") (pin "12") (pinfunction "OUT3_12") (pintype "passive"))
    )
    (net (code "81") (name "unconnected-(3-NC-Pad6)") (class "Default")
      (node (ref "3") (pin "6") (pinfunction "NC_6") (pintype "passive+no_connect"))
    )
    (net (code "82") (name "unconnected-(4-D4-Pad18)") (class "Default")
      (node (ref "4") (pin "18") (pinfunction "D4_18") (pintype "passive"))
    )
    (net (code "83") (name "unconnected-(4-IN1-Pad17)") (class "Default")
      (node (ref "4") (pin "17") (pinfunction "IN1_17") (pintype "passive"))
    )
    (net (code "84") (name "unconnected-(4-NC-Pad6)") (class "Default")
      (node (ref "4") (pin "6") (pinfunction "NC_6") (pintype "passive+no_connect"))
    )
    (net (code "85") (name "unconnected-(4-OUT4-Pad19)") (class "Default")
      (node (ref "4") (pin "19") (pinfunction "OUT4_19") (pintype "passive"))
    )
    (net (code "86") (name "unconnected-(CN1-Pad31)") (class "Default")
      (node (ref "CN1") (pin "31") (pinfunction "31_31") (pintype "passive+no_connect"))
    )
    (net (code "87") (name "unconnected-(CN1-Pad32)") (class "Default")
      (node (ref "CN1") (pin "32") (pinfunction "32_32") (pintype "passive+no_connect"))
    )
    (net (code "88") (name "unconnected-(J5-Pad1)") (class "Default")
      (node (ref "J5") (pin "1") (pinfunction "1_1") (pintype "passive"))
    )
    (net (code "89") (name "unconnected-(J5-Pad2)") (class "Default")
      (node (ref "J5") (pin "2") (pinfunction "2_2") (pintype "passive"))
    )
    (net (code "90") (name "unconnected-(J6-Pad5)") (class "Default")
      (node (ref "J6") (pin "5") (pinfunction "5_5") (pintype "passive"))
    )
    (net (code "91") (name "unconnected-(J6-Pad6)") (class "Default")
      (node (ref "J6") (pin "6") (pinfunction "6_6") (pintype "passive"))
    )
  )
)
